# launch-pad_board_schematic_r1_1.net
KiCad netlist of a schematic drawn in EasyEDA
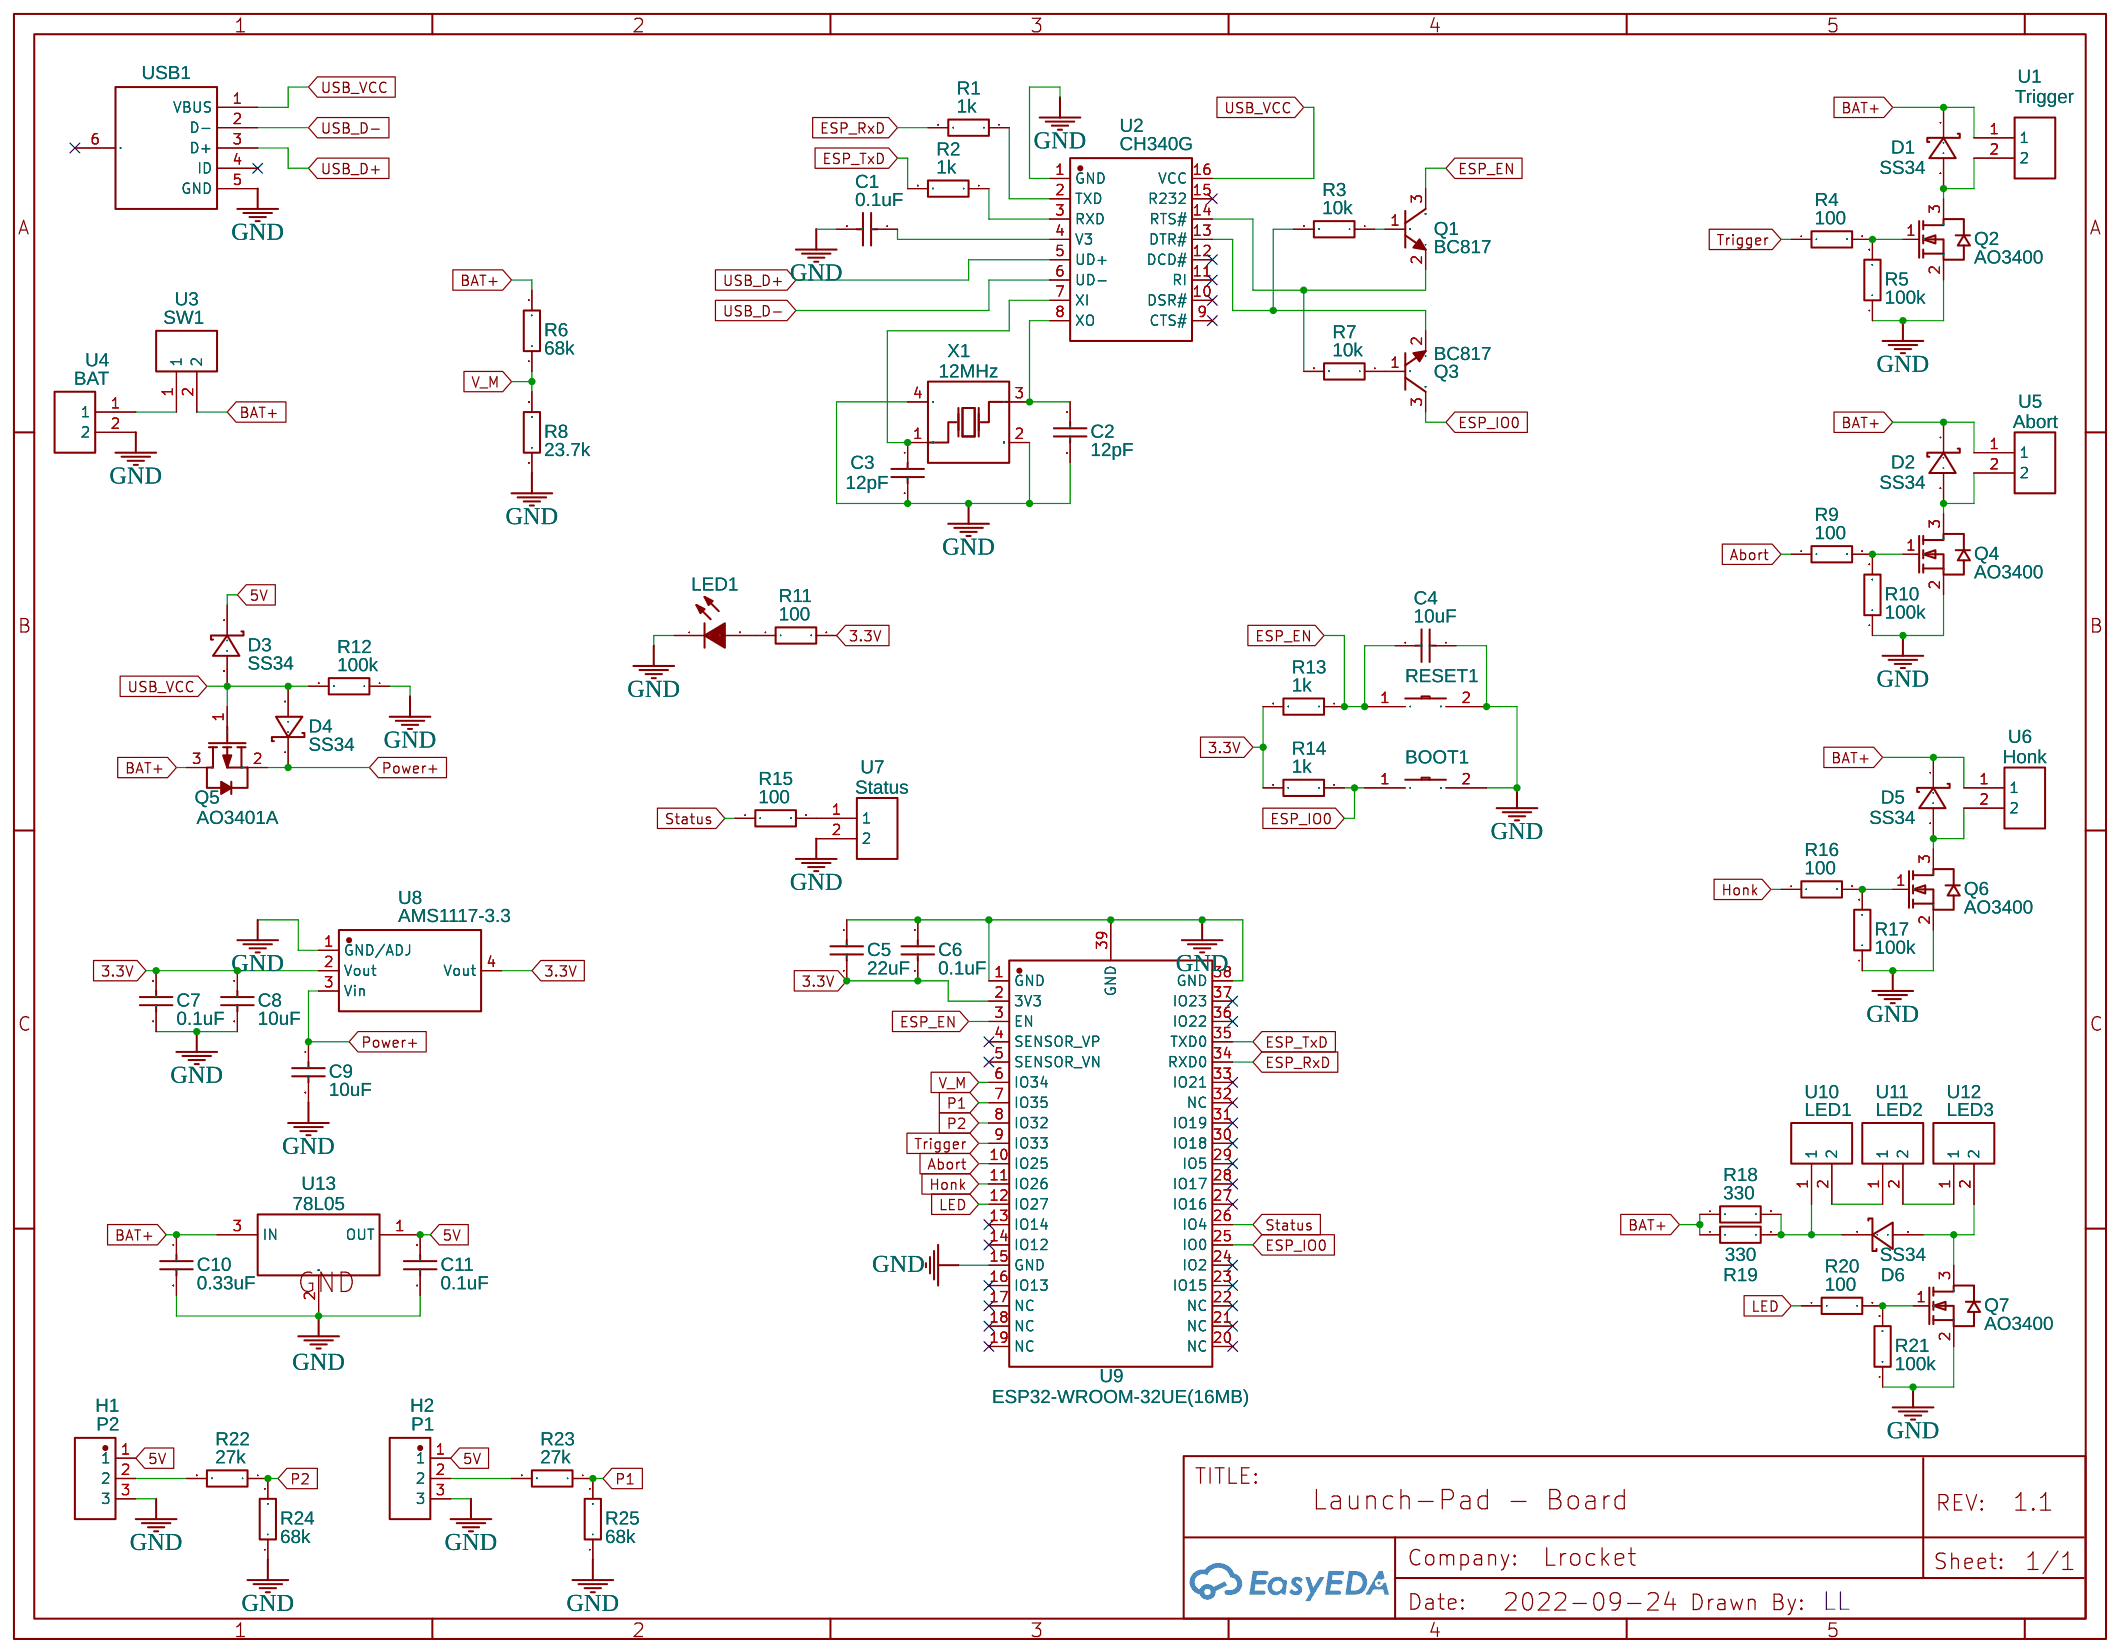
[diagram p0: schematic sheet]

(export (version "E")
  (design (tool "Eeschema 10.0.6"))
  (components
    (comp (ref "BOOT1")
      (value "TS-1101-C-W")
      (fields (field (name "BOM_Supplier Part") "C318938"))
      (libsource (lib "") (part "TS-1101-C-W"))
    )
    (comp (ref "C1")
      (value "0.1uF")
      (fields
        (field (name "BOM_Manufacturer Part") "CC0603KRX7R9BB103")
        (field (name "BOM_Supplier Part") "C100042")
      )
      (libsource (lib "") (part "CC0603KRX7R9BB103_1"))
    )
    (comp (ref "C2")
      (value "12pF")
      (fields
        (field (name "BOM_Manufacturer Part") "CC0603KRX7R9BB103")
        (field (name "BOM_Supplier Part") "C100042")
      )
      (libsource (lib "") (part "CC0603KRX7R9BB103"))
    )
    (comp (ref "C3")
      (value "12pF")
      (fields
        (field (name "BOM_Manufacturer Part") "CC0603KRX7R9BB103")
        (field (name "BOM_Supplier Part") "C100042")
      )
      (libsource (lib "") (part "CC0603KRX7R9BB103"))
    )
    (comp (ref "C4")
      (value "10uF")
      (fields
        (field (name "BOM_Manufacturer Part") "CC0603KRX7R9BB103")
        (field (name "BOM_Supplier Part") "C100042")
      )
      (libsource (lib "") (part "CC0603KRX7R9BB103_1"))
    )
    (comp (ref "C5")
      (value "22uF")
      (fields
        (field (name "BOM_Manufacturer Part") "CC0603KRX7R9BB103")
        (field (name "BOM_Supplier Part") "C100042")
      )
      (libsource (lib "") (part "CC0603KRX7R9BB103"))
    )
    (comp (ref "C6")
      (value "0.1uF")
      (fields
        (field (name "BOM_Manufacturer Part") "CC0603KRX7R9BB103")
        (field (name "BOM_Supplier Part") "C100042")
      )
      (libsource (lib "") (part "CC0603KRX7R9BB103"))
    )
    (comp (ref "C7")
      (value "0.1uF")
      (fields
        (field (name "BOM_Manufacturer Part") "CC0603KRX7R9BB103")
        (field (name "BOM_Supplier Part") "C100042")
      )
      (libsource (lib "") (part "CC0603KRX7R9BB103"))
    )
    (comp (ref "C8")
      (value "10uF")
      (fields
        (field (name "BOM_Manufacturer Part") "CC0603KRX7R9BB103")
        (field (name "BOM_Supplier Part") "C100042")
      )
      (libsource (lib "") (part "CC0603KRX7R9BB103"))
    )
    (comp (ref "C9")
      (value "10uF")
      (fields
        (field (name "BOM_Manufacturer Part") "CC0603KRX7R9BB103")
        (field (name "BOM_Supplier Part") "C100042")
      )
      (libsource (lib "") (part "CC0603KRX7R9BB103"))
    )
    (comp (ref "C10")
      (value "0.33uF")
      (fields
        (field (name "BOM_Manufacturer Part") "CC0603KRX7R9BB103")
        (field (name "BOM_Supplier Part") "C100042")
      )
      (libsource (lib "") (part "CC0603KRX7R9BB103"))
    )
    (comp (ref "C11")
      (value "0.1uF")
      (fields
        (field (name "BOM_Manufacturer Part") "CC0603KRX7R9BB103")
        (field (name "BOM_Supplier Part") "C100042")
      )
      (libsource (lib "") (part "CC0603KRX7R9BB103"))
    )
    (comp (ref "D1")
      (value "SS34")
      (fields (field (name "BOM_Supplier Part") "C8678"))
      (libsource (lib "") (part "SS34_C8678_1"))
    )
    (comp (ref "D2")
      (value "SS34")
      (fields (field (name "BOM_Supplier Part") "C8678"))
      (libsource (lib "") (part "SS34_C8678_1"))
    )
    (comp (ref "D3")
      (value "SS34")
      (fields (field (name "BOM_Supplier Part") "C8678"))
      (libsource (lib "") (part "SS34_C8678_1"))
    )
    (comp (ref "D4")
      (value "SS34")
      (fields (field (name "BOM_Supplier Part") "C8678"))
      (libsource (lib "") (part "SS34_C8678_2"))
    )
    (comp (ref "D5")
      (value "SS34")
      (fields (field (name "BOM_Supplier Part") "C8678"))
      (libsource (lib "") (part "SS34_C8678_1"))
    )
    (comp (ref "D6")
      (value "SS34")
      (fields (field (name "BOM_Supplier Part") "C8678"))
      (libsource (lib "") (part "SS34_C8678"))
    )
    (comp (ref "H1") (value "P2") (libsource (lib "") (part "3P SMD")))
    (comp (ref "H2") (value "P1") (libsource (lib "") (part "3P SMD")))
    (comp (ref "LED1")
      (value "FC-D1608WD-460H5")
      (fields (field (name "BOM_Supplier Part") "C84265"))
      (libsource (lib "") (part "FC-D1608WD-460H5"))
    )
    (comp (ref "Q1")
      (value "BC817")
      (fields (field (name "BOM_Manufacturer Part") "BC817-25") (field (name "BOM_Supplier Part") "C8588"))
      (libsource (lib "") (part "BC817-25_1"))
    )
    (comp (ref "Q2")
      (value "AO3400")
      (fields (field (name "BOM_Manufacturer Part") "AO3400A") (field (name "BOM_Supplier Part") "C347475"))
      (libsource (lib "") (part "AO3400A_C347475"))
    )
    (comp (ref "Q3")
      (value "BC817")
      (fields (field (name "BOM_Manufacturer Part") "BC817-25") (field (name "BOM_Supplier Part") "C8588"))
      (libsource (lib "") (part "BC817-25"))
    )
    (comp (ref "Q4")
      (value "AO3400")
      (fields (field (name "BOM_Manufacturer Part") "AO3400A") (field (name "BOM_Supplier Part") "C347475"))
      (libsource (lib "") (part "AO3400A_C347475"))
    )
    (comp (ref "Q5")
      (value "AO3401A")
      (fields (field (name "BOM_Supplier Part") "C15127"))
      (libsource (lib "") (part "AO3401A"))
    )
    (comp (ref "Q6")
      (value "AO3400")
      (fields (field (name "BOM_Manufacturer Part") "AO3400A") (field (name "BOM_Supplier Part") "C347475"))
      (libsource (lib "") (part "AO3400A_C347475"))
    )
    (comp (ref "Q7")
      (value "AO3400")
      (fields (field (name "BOM_Manufacturer Part") "AO3400A") (field (name "BOM_Supplier Part") "C347475"))
      (libsource (lib "") (part "AO3400A_C347475"))
    )
    (comp (ref "R1")
      (value "1k")
      (fields
        (field (name "BOM_Manufacturer Part") "TR0603B10KP05250.1W")
        (field (name "BOM_Supplier Part") "C188363")
      )
      (libsource (lib "") (part "TR0603B10KP05250.1W_2"))
    )
    (comp (ref "R2")
      (value "1k")
      (fields
        (field (name "BOM_Manufacturer Part") "TR0603B10KP05250.1W")
        (field (name "BOM_Supplier Part") "C188363")
      )
      (libsource (lib "") (part "TR0603B10KP05250.1W_2"))
    )
    (comp (ref "R3")
      (value "10k")
      (fields
        (field (name "BOM_Manufacturer Part") "TR0603B10KP05250.1W")
        (field (name "BOM_Supplier Part") "C188363")
      )
      (libsource (lib "") (part "TR0603B10KP05250.1W_2"))
    )
    (comp (ref "R4")
      (value "100")
      (fields
        (field (name "BOM_Manufacturer Part") "TR0603B10KP05250.1W")
        (field (name "BOM_Supplier Part") "C188363")
      )
      (libsource (lib "") (part "TR0603B10KP05250.1W"))
    )
    (comp (ref "R5")
      (value "100k")
      (fields
        (field (name "BOM_Manufacturer Part") "TR0603B10KP05250.1W")
        (field (name "BOM_Supplier Part") "C188363")
      )
      (libsource (lib "") (part "TR0603B10KP05250.1W_1"))
    )
    (comp (ref "R6")
      (value "68k")
      (fields
        (field (name "BOM_Manufacturer Part") "TR0603B10KP05250.1W")
        (field (name "BOM_Supplier Part") "C188363")
      )
      (libsource (lib "") (part "TR0603B10KP05250.1W_1"))
    )
    (comp (ref "R7")
      (value "10k")
      (fields
        (field (name "BOM_Manufacturer Part") "TR0603B10KP05250.1W")
        (field (name "BOM_Supplier Part") "C188363")
      )
      (libsource (lib "") (part "TR0603B10KP05250.1W_2"))
    )
    (comp (ref "R8")
      (value "23.7k")
      (fields
        (field (name "BOM_Manufacturer Part") "TR0603B10KP05250.1W")
        (field (name "BOM_Supplier Part") "C188363")
      )
      (libsource (lib "") (part "TR0603B10KP05250.1W_1"))
    )
    (comp (ref "R9")
      (value "100")
      (fields
        (field (name "BOM_Manufacturer Part") "TR0603B10KP05250.1W")
        (field (name "BOM_Supplier Part") "C188363")
      )
      (libsource (lib "") (part "TR0603B10KP05250.1W"))
    )
    (comp (ref "R10")
      (value "100k")
      (fields
        (field (name "BOM_Manufacturer Part") "TR0603B10KP05250.1W")
        (field (name "BOM_Supplier Part") "C188363")
      )
      (libsource (lib "") (part "TR0603B10KP05250.1W_1"))
    )
    (comp (ref "R11")
      (value "100")
      (fields
        (field (name "BOM_Manufacturer Part") "TR0603B10KP05250.1W")
        (field (name "BOM_Supplier Part") "C188363")
      )
      (libsource (lib "") (part "TR0603B10KP05250.1W"))
    )
    (comp (ref "R12")
      (value "100k")
      (fields
        (field (name "BOM_Manufacturer Part") "TR0603B10KP05250.1W")
        (field (name "BOM_Supplier Part") "C188363")
      )
      (libsource (lib "") (part "TR0603B10KP05250.1W_2"))
    )
    (comp (ref "R13")
      (value "1k")
      (fields
        (field (name "BOM_Manufacturer Part") "TR0603B10KP05250.1W")
        (field (name "BOM_Supplier Part") "C188363")
      )
      (libsource (lib "") (part "TR0603B10KP05250.1W_2"))
    )
    (comp (ref "R14")
      (value "1k")
      (fields
        (field (name "BOM_Manufacturer Part") "TR0603B10KP05250.1W")
        (field (name "BOM_Supplier Part") "C188363")
      )
      (libsource (lib "") (part "TR0603B10KP05250.1W_2"))
    )
    (comp (ref "R15")
      (value "100")
      (fields
        (field (name "BOM_Manufacturer Part") "TR0603B10KP05250.1W")
        (field (name "BOM_Supplier Part") "C188363")
      )
      (libsource (lib "") (part "TR0603B10KP05250.1W"))
    )
    (comp (ref "R16")
      (value "100")
      (fields
        (field (name "BOM_Manufacturer Part") "TR0603B10KP05250.1W")
        (field (name "BOM_Supplier Part") "C188363")
      )
      (libsource (lib "") (part "TR0603B10KP05250.1W"))
    )
    (comp (ref "R17")
      (value "100k")
      (fields
        (field (name "BOM_Manufacturer Part") "TR0603B10KP05250.1W")
        (field (name "BOM_Supplier Part") "C188363")
      )
      (libsource (lib "") (part "TR0603B10KP05250.1W_1"))
    )
    (comp (ref "R18")
      (value "330")
      (fields
        (field (name "BOM_Manufacturer Part") "TR0603B10KP05250.1W")
        (field (name "BOM_Supplier Part") "C188363")
      )
      (libsource (lib "") (part "TR0603B10KP05250.1W"))
    )
    (comp (ref "R19")
      (value "330")
      (fields
        (field (name "BOM_Manufacturer Part") "TR0603B10KP05250.1W")
        (field (name "BOM_Supplier Part") "C188363")
      )
      (libsource (lib "") (part "TR0603B10KP05250.1W"))
    )
    (comp (ref "R20")
      (value "100")
      (fields
        (field (name "BOM_Manufacturer Part") "TR0603B10KP05250.1W")
        (field (name "BOM_Supplier Part") "C188363")
      )
      (libsource (lib "") (part "TR0603B10KP05250.1W"))
    )
    (comp (ref "R21")
      (value "100k")
      (fields
        (field (name "BOM_Manufacturer Part") "TR0603B10KP05250.1W")
        (field (name "BOM_Supplier Part") "C188363")
      )
      (libsource (lib "") (part "TR0603B10KP05250.1W_1"))
    )
    (comp (ref "R22")
      (value "27k")
      (fields
        (field (name "BOM_Manufacturer Part") "TR0603B10KP05250.1W")
        (field (name "BOM_Supplier Part") "C188363")
      )
      (libsource (lib "") (part "TR0603B10KP05250.1W_2"))
    )
    (comp (ref "R23")
      (value "27k")
      (fields
        (field (name "BOM_Manufacturer Part") "TR0603B10KP05250.1W")
        (field (name "BOM_Supplier Part") "C188363")
      )
      (libsource (lib "") (part "TR0603B10KP05250.1W_2"))
    )
    (comp (ref "R24")
      (value "68k")
      (fields
        (field (name "BOM_Manufacturer Part") "TR0603B10KP05250.1W")
        (field (name "BOM_Supplier Part") "C188363")
      )
      (libsource (lib "") (part "TR0603B10KP05250.1W_1"))
    )
    (comp (ref "R25")
      (value "68k")
      (fields
        (field (name "BOM_Manufacturer Part") "TR0603B10KP05250.1W")
        (field (name "BOM_Supplier Part") "C188363")
      )
      (libsource (lib "") (part "TR0603B10KP05250.1W_1"))
    )
    (comp (ref "RESET1")
      (value "TS-1101-C-W")
      (fields (field (name "BOM_Supplier Part") "C318938"))
      (libsource (lib "") (part "TS-1101-C-W_1"))
    )
    (comp (ref "U1")
      (value "Trigger")
      (fields (field (name "BOM_Manufacturer Part") "WGGM"))
      (libsource (lib "") (part "HEADER_SMD2"))
    )
    (comp (ref "U2")
      (value "CH340G")
      (fields (field (name "BOM_Supplier Part") "C14267"))
      (libsource (lib "") (part "CH340G"))
    )
    (comp (ref "U3")
      (value "SW1")
      (fields (field (name "BOM_Manufacturer Part") "WGGM"))
      (libsource (lib "") (part "HEADER_SMD2_2"))
    )
    (comp (ref "U4")
      (value "BAT")
      (fields (field (name "BOM_Manufacturer Part") "WGGM"))
      (libsource (lib "") (part "HEADER_SMD2_1"))
    )
    (comp (ref "U5")
      (value "Abort")
      (fields (field (name "BOM_Manufacturer Part") "WGGM"))
      (libsource (lib "") (part "HEADER_SMD2"))
    )
    (comp (ref "U6")
      (value "Honk")
      (fields (field (name "BOM_Manufacturer Part") "WGGM"))
      (libsource (lib "") (part "HEADER_SMD2"))
    )
    (comp (ref "U7")
      (value "Status")
      (fields (field (name "BOM_Manufacturer Part") "WGGM"))
      (libsource (lib "") (part "HEADER_SMD2"))
    )
    (comp (ref "U8")
      (value "AMS1117-3.3")
      (fields (field (name "BOM_Supplier Part") "C6186"))
      (libsource (lib "") (part "AMS1117-3.3"))
    )
    (comp (ref "U9")
      (value "ESP32-WROOM-32UE(16MB)")
      (fields (field (name "BOM_Supplier Part") "C701346"))
      (libsource (lib "") (part "ESP32-WROOM-32UE(16MB)"))
    )
    (comp (ref "U10")
      (value "LED1")
      (fields (field (name "BOM_Manufacturer Part") "WGGM"))
      (libsource (lib "") (part "HEADER_SMD2_2"))
    )
    (comp (ref "U11")
      (value "LED2")
      (fields (field (name "BOM_Manufacturer Part") "WGGM"))
      (libsource (lib "") (part "HEADER_SMD2_2"))
    )
    (comp (ref "U12")
      (value "LED3")
      (fields (field (name "BOM_Manufacturer Part") "WGGM"))
      (libsource (lib "") (part "HEADER_SMD2_2"))
    )
    (comp (ref "U13")
      (value "78L05")
      (fields (field (name "BOM_Manufacturer Part") "UMW78L05") (field (name "BOM_Supplier Part") "C347258"))
      (libsource (lib "") (part "UMW78L05"))
    )
    (comp (ref "USB1")
      (value "USB1")
      (fields
        (field (name "BOM_Manufacturer Part") "U254-051T-4BH83-S1S")
        (field (name "BOM_Supplier Part") "C319160")
      )
      (libsource (lib "") (part "U254-051T-4BH83-S1S"))
    )
    (comp (ref "X1")
      (value "12MHz")
      (fields
        (field (name "BOM_Manufacturer Part") "X322512MOB4SI")
        (field (name "BOM_Supplier Part") "C70565")
      )
      (libsource (lib "") (part "X322512MOB4SI"))
    )
  )
  (nets
    (net (code "1") (name "3.3V") (class "Default")
      (node (ref "C5") (pin "2") (pinfunction "2_2") (pintype "input"))
      (node (ref "C6") (pin "2") (pinfunction "2_2") (pintype "input"))
      (node (ref "C7") (pin "1") (pinfunction "1_1") (pintype "input"))
      (node (ref "C8") (pin "1") (pinfunction "1_1") (pintype "input"))
      (node (ref "R11") (pin "2") (pinfunction "2_2") (pintype "unspecified"))
      (node (ref "R13") (pin "2") (pinfunction "2_2") (pintype "unspecified"))
      (node (ref "R14") (pin "2") (pinfunction "2_2") (pintype "unspecified"))
      (node (ref "U8") (pin "2") (pinfunction "Vout_2") (pintype "unspecified"))
      (node (ref "U8") (pin "4") (pinfunction "Vout_4") (pintype "unspecified"))
      (node (ref "U9") (pin "2") (pinfunction "3V3_2") (pintype "unspecified"))
    )
    (net (code "2") (name "5V") (class "Default")
      (node (ref "C11") (pin "1") (pinfunction "1_1") (pintype "input"))
      (node (ref "D3") (pin "1") (pinfunction "K_1") (pintype "unspecified"))
      (node (ref "H1") (pin "1") (pinfunction "1_1") (pintype "unspecified"))
      (node (ref "H2") (pin "1") (pinfunction "1_1") (pintype "unspecified"))
      (node (ref "U13") (pin "1") (pinfunction "OUT_1") (pintype "passive"))
    )
    (net (code "3") (name "Abort") (class "Default")
      (node (ref "R9") (pin "1") (pinfunction "1_1") (pintype "unspecified"))
      (node (ref "U9") (pin "10") (pinfunction "IO25_10") (pintype "unspecified"))
    )
    (net (code "4") (name "BAT+") (class "Default")
      (node (ref "C10") (pin "1") (pinfunction "1_1") (pintype "input"))
      (node (ref "D1") (pin "1") (pinfunction "K_1") (pintype "unspecified"))
      (node (ref "D2") (pin "1") (pinfunction "K_1") (pintype "unspecified"))
      (node (ref "D5") (pin "1") (pinfunction "K_1") (pintype "unspecified"))
      (node (ref "Q5") (pin "3") (pinfunction "D_3") (pintype "unspecified"))
      (node (ref "R18") (pin "1") (pinfunction "1_1") (pintype "unspecified"))
      (node (ref "R19") (pin "1") (pinfunction "1_1") (pintype "unspecified"))
      (node (ref "R6") (pin "2") (pinfunction "2_2") (pintype "unspecified"))
      (node (ref "U1") (pin "1") (pinfunction "1_1") (pintype "unspecified"))
      (node (ref "U13") (pin "3") (pinfunction "IN_3") (pintype "passive"))
      (node (ref "U3") (pin "2") (pinfunction "2_2") (pintype "unspecified"))
      (node (ref "U5") (pin "1") (pinfunction "1_1") (pintype "unspecified"))
      (node (ref "U6") (pin "1") (pinfunction "1_1") (pintype "unspecified"))
    )
    (net (code "5") (name "ESP_EN") (class "Default")
      (node (ref "C4") (pin "2") (pinfunction "2_2") (pintype "input"))
      (node (ref "Q1") (pin "3") (pinfunction "C_3") (pintype "unspecified"))
      (node (ref "R13") (pin "1") (pinfunction "1_1") (pintype "unspecified"))
      (node (ref "RESET1") (pin "1") (pinfunction "1_1") (pintype "unspecified"))
      (node (ref "U9") (pin "3") (pinfunction "EN_3") (pintype "unspecified"))
    )
    (net (code "6") (name "ESP_IO0") (class "Default")
      (node (ref "BOOT1") (pin "1") (pinfunction "1_1") (pintype "unspecified"))
      (node (ref "Q3") (pin "3") (pinfunction "C_3") (pintype "unspecified"))
      (node (ref "R14") (pin "1") (pinfunction "1_1") (pintype "unspecified"))
      (node (ref "U9") (pin "25") (pinfunction "IO0_25") (pintype "unspecified"))
    )
    (net (code "7") (name "ESP_RxD") (class "Default")
      (node (ref "R1") (pin "2") (pinfunction "2_2") (pintype "unspecified"))
      (node (ref "U9") (pin "34") (pinfunction "RXD0_34") (pintype "unspecified"))
    )
    (net (code "8") (name "ESP_TxD") (class "Default")
      (node (ref "R2") (pin "2") (pinfunction "2_2") (pintype "unspecified"))
      (node (ref "U9") (pin "35") (pinfunction "TXD0_35") (pintype "unspecified"))
    )
    (net (code "9") (name "GND") (class "Default")
      (node (ref "BOOT1") (pin "2") (pinfunction "2_2") (pintype "unspecified"))
      (node (ref "C1") (pin "2") (pinfunction "2_2") (pintype "input"))
      (node (ref "C10") (pin "2") (pinfunction "2_2") (pintype "input"))
      (node (ref "C11") (pin "2") (pinfunction "2_2") (pintype "input"))
      (node (ref "C2") (pin "2") (pinfunction "2_2") (pintype "input"))
      (node (ref "C3") (pin "2") (pinfunction "2_2") (pintype "input"))
      (node (ref "C4") (pin "1") (pinfunction "1_1") (pintype "input"))
      (node (ref "C5") (pin "1") (pinfunction "1_1") (pintype "input"))
      (node (ref "C6") (pin "1") (pinfunction "1_1") (pintype "input"))
      (node (ref "C7") (pin "2") (pinfunction "2_2") (pintype "input"))
      (node (ref "C8") (pin "2") (pinfunction "2_2") (pintype "input"))
      (node (ref "C9") (pin "2") (pinfunction "2_2") (pintype "input"))
      (node (ref "H1") (pin "3") (pinfunction "3_3") (pintype "unspecified"))
      (node (ref "H2") (pin "3") (pinfunction "3_3") (pintype "unspecified"))
      (node (ref "LED1") (pin "1") (pinfunction "-_1") (pintype "input"))
      (node (ref "Q2") (pin "2") (pinfunction "S_2") (pintype "unspecified"))
      (node (ref "Q4") (pin "2") (pinfunction "S_2") (pintype "unspecified"))
      (node (ref "Q6") (pin "2") (pinfunction "S_2") (pintype "unspecified"))
      (node (ref "Q7") (pin "2") (pinfunction "S_2") (pintype "unspecified"))
      (node (ref "R10") (pin "1") (pinfunction "1_1") (pintype "unspecified"))
      (node (ref "R12") (pin "1") (pinfunction "1_1") (pintype "unspecified"))
      (node (ref "R17") (pin "1") (pinfunction "1_1") (pintype "unspecified"))
      (node (ref "R21") (pin "1") (pinfunction "1_1") (pintype "unspecified"))
      (node (ref "R24") (pin "1") (pinfunction "1_1") (pintype "unspecified"))
      (node (ref "R25") (pin "1") (pinfunction "1_1") (pintype "unspecified"))
      (node (ref "R5") (pin "1") (pinfunction "1_1") (pintype "unspecified"))
      (node (ref "R8") (pin "1") (pinfunction "1_1") (pintype "unspecified"))
      (node (ref "RESET1") (pin "2") (pinfunction "2_2") (pintype "unspecified"))
      (node (ref "U13") (pin "2") (pinfunction "GND_2") (pintype "passive"))
      (node (ref "U2") (pin "1") (pinfunction "GND_1") (pintype "unspecified"))
      (node (ref "U4") (pin "2") (pinfunction "2_2") (pintype "unspecified"))
      (node (ref "U7") (pin "2") (pinfunction "2_2") (pintype "unspecified"))
      (node (ref "U8") (pin "1") (pinfunction "GND/ADJ_1") (pintype "unspecified"))
      (node (ref "U9") (pin "1") (pinfunction "GND_1") (pintype "unspecified"))
      (node (ref "U9") (pin "15") (pinfunction "GND_15") (pintype "unspecified"))
      (node (ref "U9") (pin "38") (pinfunction "GND_38") (pintype "unspecified"))
      (node (ref "U9") (pin "39") (pinfunction "GND_39") (pintype "unspecified"))
      (node (ref "USB1") (pin "5") (pinfunction "GND_5") (pintype "input"))
      (node (ref "X1") (pin "2") (pinfunction "GND_2") (pintype "unspecified"))
      (node (ref "X1") (pin "4") (pinfunction "GND_4") (pintype "unspecified"))
    )
    (net (code "10") (name "Honk") (class "Default")
      (node (ref "R16") (pin "1") (pinfunction "1_1") (pintype "unspecified"))
      (node (ref "U9") (pin "11") (pinfunction "IO26_11") (pintype "unspecified"))
    )
    (net (code "11") (name "LED") (class "Default")
      (node (ref "R20") (pin "1") (pinfunction "1_1") (pintype "unspecified"))
      (node (ref "U9") (pin "12") (pinfunction "IO27_12") (pintype "unspecified"))
    )
    (net (code "12") (name "Net-(D1-A)") (class "Default")
      (node (ref "D1") (pin "2") (pinfunction "A_2") (pintype "unspecified"))
      (node (ref "Q2") (pin "3") (pinfunction "D_3") (pintype "unspecified"))
      (node (ref "U1") (pin "2") (pinfunction "2_2") (pintype "unspecified"))
    )
    (net (code "13") (name "Net-(D2-A)") (class "Default")
      (node (ref "D2") (pin "2") (pinfunction "A_2") (pintype "unspecified"))
      (node (ref "Q4") (pin "3") (pinfunction "D_3") (pintype "unspecified"))
      (node (ref "U5") (pin "2") (pinfunction "2_2") (pintype "unspecified"))
    )
    (net (code "14") (name "Net-(D5-A)") (class "Default")
      (node (ref "D5") (pin "2") (pinfunction "A_2") (pintype "unspecified"))
      (node (ref "Q6") (pin "3") (pinfunction "D_3") (pintype "unspecified"))
      (node (ref "U6") (pin "2") (pinfunction "2_2") (pintype "unspecified"))
    )
    (net (code "15") (name "Net-(D6-A)") (class "Default")
      (node (ref "D6") (pin "2") (pinfunction "A_2") (pintype "unspecified"))
      (node (ref "Q7") (pin "3") (pinfunction "D_3") (pintype "unspecified"))
      (node (ref "U12") (pin "2") (pinfunction "2_2") (pintype "unspecified"))
    )
    (net (code "16") (name "Net-(D6-K)") (class "Default")
      (node (ref "D6") (pin "1") (pinfunction "K_1") (pintype "unspecified"))
      (node (ref "R18") (pin "2") (pinfunction "2_2") (pintype "unspecified"))
      (node (ref "R19") (pin "2") (pinfunction "2_2") (pintype "unspecified"))
      (node (ref "U10") (pin "1") (pinfunction "1_1") (pintype "unspecified"))
    )
    (net (code "17") (name "Net-(H1-Pad2)") (class "Default")
      (node (ref "H1") (pin "2") (pinfunction "2_2") (pintype "unspecified"))
      (node (ref "R22") (pin "2") (pinfunction "2_2") (pintype "unspecified"))
    )
    (net (code "18") (name "Net-(H2-Pad2)") (class "Default")
      (node (ref "H2") (pin "2") (pinfunction "2_2") (pintype "unspecified"))
      (node (ref "R23") (pin "2") (pinfunction "2_2") (pintype "unspecified"))
    )
    (net (code "19") (name "Net-(LED1-+)") (class "Default")
      (node (ref "LED1") (pin "2") (pinfunction "+_2") (pintype "input"))
      (node (ref "R11") (pin "1") (pinfunction "1_1") (pintype "unspecified"))
    )
    (net (code "20") (name "Net-(Q1-B)") (class "Default")
      (node (ref "Q1") (pin "1") (pinfunction "B_1") (pintype "unspecified"))
      (node (ref "R3") (pin "1") (pinfunction "1_1") (pintype "unspecified"))
    )
    (net (code "21") (name "Net-(Q1-E)") (class "Default")
      (node (ref "Q1") (pin "2") (pinfunction "E_2") (pintype "unspecified"))
      (node (ref "R7") (pin "2") (pinfunction "2_2") (pintype "unspecified"))
      (node (ref "U2") (pin "14") (pinfunction "RTS#_14") (pintype "unspecified"))
    )
    (net (code "22") (name "Net-(Q2-G)") (class "Default")
      (node (ref "Q2") (pin "1") (pinfunction "G_1") (pintype "unspecified"))
      (node (ref "R4") (pin "2") (pinfunction "2_2") (pintype "unspecified"))
      (node (ref "R5") (pin "2") (pinfunction "2_2") (pintype "unspecified"))
    )
    (net (code "23") (name "Net-(Q3-B)") (class "Default")
      (node (ref "Q3") (pin "1") (pinfunction "B_1") (pintype "unspecified"))
      (node (ref "R7") (pin "1") (pinfunction "1_1") (pintype "unspecified"))
    )
    (net (code "24") (name "Net-(Q3-E)") (class "Default")
      (node (ref "Q3") (pin "2") (pinfunction "E_2") (pintype "unspecified"))
      (node (ref "R3") (pin "2") (pinfunction "2_2") (pintype "unspecified"))
      (node (ref "U2") (pin "13") (pinfunction "DTR#_13") (pintype "unspecified"))
    )
    (net (code "25") (name "Net-(Q4-G)") (class "Default")
      (node (ref "Q4") (pin "1") (pinfunction "G_1") (pintype "unspecified"))
      (node (ref "R10") (pin "2") (pinfunction "2_2") (pintype "unspecified"))
      (node (ref "R9") (pin "2") (pinfunction "2_2") (pintype "unspecified"))
    )
    (net (code "26") (name "Net-(Q6-G)") (class "Default")
      (node (ref "Q6") (pin "1") (pinfunction "G_1") (pintype "unspecified"))
      (node (ref "R16") (pin "2") (pinfunction "2_2") (pintype "unspecified"))
      (node (ref "R17") (pin "2") (pinfunction "2_2") (pintype "unspecified"))
    )
    (net (code "27") (name "Net-(Q7-G)") (class "Default")
      (node (ref "Q7") (pin "1") (pinfunction "G_1") (pintype "unspecified"))
      (node (ref "R20") (pin "2") (pinfunction "2_2") (pintype "unspecified"))
      (node (ref "R21") (pin "2") (pinfunction "2_2") (pintype "unspecified"))
    )
    (net (code "28") (name "Net-(R15-Pad2)") (class "Default")
      (node (ref "R15") (pin "2") (pinfunction "2_2") (pintype "unspecified"))
      (node (ref "U7") (pin "1") (pinfunction "1_1") (pintype "unspecified"))
    )
    (net (code "29") (name "Net-(U2-RXD)") (class "Default")
      (node (ref "R2") (pin "1") (pinfunction "1_1") (pintype "unspecified"))
      (node (ref "U2") (pin "3") (pinfunction "RXD_3") (pintype "unspecified"))
    )
    (net (code "30") (name "Net-(U2-TXD)") (class "Default")
      (node (ref "R1") (pin "1") (pinfunction "1_1") (pintype "unspecified"))
      (node (ref "U2") (pin "2") (pinfunction "TXD_2") (pintype "unspecified"))
    )
    (net (code "31") (name "Net-(U2-V3)") (class "Default")
      (node (ref "C1") (pin "1") (pinfunction "1_1") (pintype "input"))
      (node (ref "U2") (pin "4") (pinfunction "V3_4") (pintype "unspecified"))
    )
    (net (code "32") (name "Net-(U2-XI)") (class "Default")
      (node (ref "C3") (pin "1") (pinfunction "1_1") (pintype "input"))
      (node (ref "U2") (pin "7") (pinfunction "XI_7") (pintype "unspecified"))
      (node (ref "X1") (pin "1") (pinfunction "OSC1_1") (pintype "unspecified"))
    )
    (net (code "33") (name "Net-(U2-XO)") (class "Default")
      (node (ref "C2") (pin "1") (pinfunction "1_1") (pintype "input"))
      (node (ref "U2") (pin "8") (pinfunction "XO_8") (pintype "unspecified"))
      (node (ref "X1") (pin "3") (pinfunction "OSC2_3") (pintype "unspecified"))
    )
    (net (code "34") (name "Net-(U3-Pad1)") (class "Default")
      (node (ref "U3") (pin "1") (pinfunction "1_1") (pintype "unspecified"))
      (node (ref "U4") (pin "1") (pinfunction "1_1") (pintype "unspecified"))
    )
    (net (code "35") (name "Net-(U10-Pad2)") (class "Default")
      (node (ref "U10") (pin "2") (pinfunction "2_2") (pintype "unspecified"))
      (node (ref "U11") (pin "1") (pinfunction "1_1") (pintype "unspecified"))
    )
    (net (code "36") (name "Net-(U11-Pad2)") (class "Default")
      (node (ref "U11") (pin "2") (pinfunction "2_2") (pintype "unspecified"))
      (node (ref "U12") (pin "1") (pinfunction "1_1") (pintype "unspecified"))
    )
    (net (code "37") (name "P1") (class "Default")
      (node (ref "R23") (pin "1") (pinfunction "1_1") (pintype "unspecified"))
      (node (ref "R25") (pin "2") (pinfunction "2_2") (pintype "unspecified"))
      (node (ref "U9") (pin "7") (pinfunction "IO35_7") (pintype "unspecified"))
    )
    (net (code "38") (name "P2") (class "Default")
      (node (ref "R22") (pin "1") (pinfunction "1_1") (pintype "unspecified"))
      (node (ref "R24") (pin "2") (pinfunction "2_2") (pintype "unspecified"))
      (node (ref "U9") (pin "8") (pinfunction "IO32_8") (pintype "unspecified"))
    )
    (net (code "39") (name "Power+") (class "Default")
      (node (ref "C9") (pin "1") (pinfunction "1_1") (pintype "input"))
      (node (ref "D4") (pin "1") (pinfunction "K_1") (pintype "unspecified"))
      (node (ref "Q5") (pin "2") (pinfunction "S_2") (pintype "unspecified"))
      (node (ref "U8") (pin "3") (pinfunction "Vin_3") (pintype "unspecified"))
    )
    (net (code "40") (name "Status") (class "Default")
      (node (ref "R15") (pin "1") (pinfunction "1_1") (pintype "unspecified"))
      (node (ref "U9") (pin "26") (pinfunction "IO4_26") (pintype "unspecified"))
    )
    (net (code "41") (name "Trigger") (class "Default")
      (node (ref "R4") (pin "1") (pinfunction "1_1") (pintype "unspecified"))
      (node (ref "U9") (pin "9") (pinfunction "IO33_9") (pintype "unspecified"))
    )
    (net (code "42") (name "USB_D+") (class "Default")
      (node (ref "U2") (pin "5") (pinfunction "UD+_5") (pintype "unspecified"))
      (node (ref "USB1") (pin "3") (pinfunction "D+_3") (pintype "input"))
    )
    (net (code "43") (name "USB_D-") (class "Default")
      (node (ref "U2") (pin "6") (pinfunction "UD-_6") (pintype "unspecified"))
      (node (ref "USB1") (pin "2") (pinfunction "D-_2") (pintype "input"))
    )
    (net (code "44") (name "USB_VCC") (class "Default")
      (node (ref "D3") (pin "2") (pinfunction "A_2") (pintype "unspecified"))
      (node (ref "D4") (pin "2") (pinfunction "A_2") (pintype "unspecified"))
      (node (ref "Q5") (pin "1") (pinfunction "G_1") (pintype "unspecified"))
      (node (ref "R12") (pin "2") (pinfunction "2_2") (pintype "unspecified"))
      (node (ref "U2") (pin "16") (pinfunction "VCC_16") (pintype "unspecified"))
      (node (ref "USB1") (pin "1") (pinfunction "VBUS_1") (pintype "input"))
    )
    (net (code "45") (name "V_M") (class "Default")
      (node (ref "R6") (pin "1") (pinfunction "1_1") (pintype "unspecified"))
      (node (ref "R8") (pin "2") (pinfunction "2_2") (pintype "unspecified"))
      (node (ref "U9") (pin "6") (pinfunction "IO34_6") (pintype "unspecified"))
    )
    (net (code "46") (name "unconnected-(U2-CTS#-Pad9)") (class "Default")
      (node (ref "U2") (pin "9") (pinfunction "CTS#_9") (pintype "unspecified+no_connect"))
    )
    (net (code "47") (name "unconnected-(U2-DCD#-Pad12)") (class "Default")
      (node (ref "U2") (pin "12") (pinfunction "DCD#_12") (pintype "unspecified+no_connect"))
    )
    (net (code "48") (name "unconnected-(U2-DSR#-Pad10)") (class "Default")
      (node (ref "U2") (pin "10") (pinfunction "DSR#_10") (pintype "unspecified+no_connect"))
    )
    (net (code "49") (name "unconnected-(U2-R232-Pad15)") (class "Default")
      (node (ref "U2") (pin "15") (pinfunction "R232_15") (pintype "unspecified+no_connect"))
    )
    (net (code "50") (name "unconnected-(U2-RI-Pad11)") (class "Default")
      (node (ref "U2") (pin "11") (pinfunction "RI_11") (pintype "unspecified+no_connect"))
    )
    (net (code "51") (name "unconnected-(U9-IO2-Pad24)") (class "Default")
      (node (ref "U9") (pin "24") (pinfunction "IO2_24") (pintype "unspecified+no_connect"))
    )
    (net (code "52") (name "unconnected-(U9-IO5-Pad29)") (class "Default")
      (node (ref "U9") (pin "29") (pinfunction "IO5_29") (pintype "unspecified+no_connect"))
    )
    (net (code "53") (name "unconnected-(U9-IO12-Pad14)") (class "Default")
      (node (ref "U9") (pin "14") (pinfunction "IO12_14") (pintype "unspecified+no_connect"))
    )
    (net (code "54") (name "unconnected-(U9-IO13-Pad16)") (class "Default")
      (node (ref "U9") (pin "16") (pinfunction "IO13_16") (pintype "unspecified+no_connect"))
    )
    (net (code "55") (name "unconnected-(U9-IO14-Pad13)") (class "Default")
      (node (ref "U9") (pin "13") (pinfunction "IO14_13") (pintype "unspecified+no_connect"))
    )
    (net (code "56") (name "unconnected-(U9-IO15-Pad23)") (class "Default")
      (node (ref "U9") (pin "23") (pinfunction "IO15_23") (pintype "unspecified+no_connect"))
    )
    (net (code "57") (name "unconnected-(U9-IO16-Pad27)") (class "Default")
      (node (ref "U9") (pin "27") (pinfunction "IO16_27") (pintype "unspecified+no_connect"))
    )
    (net (code "58") (name "unconnected-(U9-IO17-Pad28)") (class "Default")
      (node (ref "U9") (pin "28") (pinfunction "IO17_28") (pintype "unspecified+no_connect"))
    )
    (net (code "59") (name "unconnected-(U9-IO18-Pad30)") (class "Default")
      (node (ref "U9") (pin "30") (pinfunction "IO18_30") (pintype "unspecified+no_connect"))
    )
    (net (code "60") (name "unconnected-(U9-IO19-Pad31)") (class "Default")
      (node (ref "U9") (pin "31") (pinfunction "IO19_31") (pintype "unspecified+no_connect"))
    )
    (net (code "61") (name "unconnected-(U9-IO21-Pad33)") (class "Default")
      (node (ref "U9") (pin "33") (pinfunction "IO21_33") (pintype "unspecified+no_connect"))
    )
    (net (code "62") (name "unconnected-(U9-IO22-Pad36)") (class "Default")
      (node (ref "U9") (pin "36") (pinfunction "IO22_36") (pintype "unspecified+no_connect"))
    )
    (net (code "63") (name "unconnected-(U9-IO23-Pad37)") (class "Default")
      (node (ref "U9") (pin "37") (pinfunction "IO23_37") (pintype "unspecified+no_connect"))
    )
    (net (code "64") (name "unconnected-(U9-NC-Pad17)") (class "Default")
      (node (ref "U9") (pin "17") (pinfunction "NC_17") (pintype "unspecified+no_connect"))
    )
    (net (code "65") (name "unconnected-(U9-NC-Pad18)") (class "Default")
      (node (ref "U9") (pin "18") (pinfunction "NC_18") (pintype "unspecified+no_connect"))
    )
    (net (code "66") (name "unconnected-(U9-NC-Pad19)") (class "Default")
      (node (ref "U9") (pin "19") (pinfunction "NC_19") (pintype "unspecified+no_connect"))
    )
    (net (code "67") (name "unconnected-(U9-NC-Pad20)") (class "Default")
      (node (ref "U9") (pin "20") (pinfunction "NC_20") (pintype "unspecified+no_connect"))
    )
    (net (code "68") (name "unconnected-(U9-NC-Pad21)") (class "Default")
      (node (ref "U9") (pin "21") (pinfunction "NC_21") (pintype "unspecified+no_connect"))
    )
    (net (code "69") (name "unconnected-(U9-NC-Pad22)") (class "Default")
      (node (ref "U9") (pin "22") (pinfunction "NC_22") (pintype "unspecified+no_connect"))
    )
    (net (code "70") (name "unconnected-(U9-NC-Pad32)") (class "Default")
      (node (ref "U9") (pin "32") (pinfunction "NC_32") (pintype "unspecified+no_connect"))
    )
    (net (code "71") (name "unconnected-(U9-SENSOR_VN-Pad5)") (class "Default")
      (node (ref "U9") (pin "5") (pinfunction "SENSOR_VN_5") (pintype "unspecified+no_connect"))
    )
    (net (code "72") (name "unconnected-(U9-SENSOR_VP-Pad4)") (class "Default")
      (node (ref "U9") (pin "4") (pinfunction "SENSOR_VP_4") (pintype "unspecified+no_connect"))
    )
    (net (code "73") (name "unconnected-(USB1-EH-Pad6)") (class "Default")
      (node (ref "USB1") (pin "6") (pinfunction "EH_6") (pintype "input+no_connect"))
    )
    (net (code "74") (name "unconnected-(USB1-ID-Pad4)") (class "Default")
      (node (ref "USB1") (pin "4") (pinfunction "ID_4") (pintype "input+no_connect"))
    )
  )
)
